# Screen.net
KiCad netlist of a schematic drawn in Altium Designer
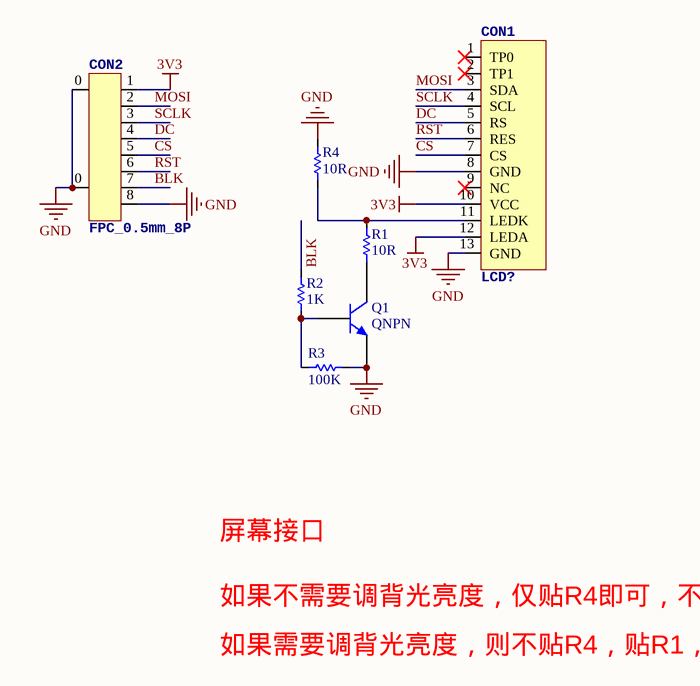
[diagram p0: Screen.SchDoc]

(export (version "E")
  (design (tool "Eeschema 10.0.6"))
  (components
    (comp (ref "CON1")
      (value "LCD?")
      (footprint "LCD_ST7735")
      (description "屏幕排线接口")
      (libsource (lib "Screen") (part "LCD_ST7735"))
    )
    (comp (ref "CON2")
      (value "FPC_0.5mm_8P")
      (footprint "FFC_0.5_8")
      (description "FPC连接器")
      (libsource (lib "Screen") (part "FPC_0.5mm_8P"))
    )
    (comp (ref "Q1")
      (value "QNPN")
      (footprint "SOT-23B_N")
      (description "NPN Bipolar Transistor")
      (fields (field (name "PUBLISHER") "Altium Limited"))
      (libsource (lib "Miscellaneous Devices") (part "QNPN"))
    )
    (comp (ref "R1")
      (value "10R")
      (footprint "RESC_0402")
      (description "贴片电阻")
      (libsource (lib "Screen") (part "电阻-0402"))
    )
    (comp (ref "R2")
      (value "1K")
      (footprint "RESC_0402")
      (description "贴片电阻")
      (libsource (lib "Screen") (part "电阻-0402"))
    )
    (comp (ref "R3")
      (value "100K")
      (footprint "RESC_0402")
      (description "贴片电阻")
      (libsource (lib "Screen") (part "电阻-0402"))
    )
    (comp (ref "R4")
      (value "10R")
      (footprint "RESC_0402")
      (description "贴片电阻")
      (libsource (lib "Screen") (part "电阻-0402"))
    )
  )
  (nets
    (net (code "1") (name "/BLK") (class "Default")
      (node (ref "CON2") (pin "7") (pinfunction "7_7") (pintype "passive"))
      (node (ref "R2") (pin "2") (pinfunction "2_2") (pintype "passive"))
    )
    (net (code "2") (name "/CS") (class "Default")
      (node (ref "CON1") (pin "7") (pinfunction "CS_7") (pintype "passive"))
      (node (ref "CON2") (pin "5") (pinfunction "5_5") (pintype "passive"))
    )
    (net (code "3") (name "/DC") (class "Default")
      (node (ref "CON1") (pin "5") (pinfunction "RS_5") (pintype "passive"))
      (node (ref "CON2") (pin "4") (pinfunction "4_4") (pintype "passive"))
    )
    (net (code "4") (name "/MOSI") (class "Default")
      (node (ref "CON1") (pin "3") (pinfunction "SDA_3") (pintype "passive"))
      (node (ref "CON2") (pin "2") (pinfunction "2_2") (pintype "passive"))
    )
    (net (code "5") (name "/RST") (class "Default")
      (node (ref "CON1") (pin "6") (pinfunction "RES_6") (pintype "passive"))
      (node (ref "CON2") (pin "6") (pinfunction "6_6") (pintype "passive"))
    )
    (net (code "6") (name "/SCLK") (class "Default")
      (node (ref "CON1") (pin "4") (pinfunction "SCL_4") (pintype "passive"))
      (node (ref "CON2") (pin "3") (pinfunction "3_3") (pintype "passive"))
    )
    (net (code "7") (name "3V3") (class "Default")
      (node (ref "CON1") (pin "10") (pinfunction "VCC_10") (pintype "passive"))
      (node (ref "CON1") (pin "12") (pinfunction "LEDA_12") (pintype "passive"))
      (node (ref "CON2") (pin "1") (pinfunction "1_1") (pintype "passive"))
    )
    (net (code "8") (name "GND") (class "Default")
      (node (ref "CON1") (pin "13") (pinfunction "GND_13") (pintype "passive"))
      (node (ref "CON1") (pin "8") (pinfunction "GND_8") (pintype "passive"))
      (node (ref "CON2") (pin "0") (pinfunction "0_0") (pintype "passive"))
      (node (ref "CON2") (pin "8") (pinfunction "8_8") (pintype "passive"))
      (node (ref "Q1") (pin "3") (pinfunction "E_3") (pintype "passive"))
      (node (ref "R3") (pin "2") (pinfunction "2_2") (pintype "passive"))
      (node (ref "R4") (pin "2") (pinfunction "2_2") (pintype "passive"))
    )
    (net (code "9") (name "Net-(CON1-LEDK)") (class "Default")
      (node (ref "CON1") (pin "11") (pinfunction "LEDK_11") (pintype "passive"))
      (node (ref "R1") (pin "2") (pinfunction "2_2") (pintype "passive"))
      (node (ref "R4") (pin "1") (pinfunction "1_1") (pintype "passive"))
    )
    (net (code "10") (name "Net-(Q1-B)") (class "Default")
      (node (ref "Q1") (pin "2") (pinfunction "B_2") (pintype "passive"))
      (node (ref "R2") (pin "1") (pinfunction "1_1") (pintype "passive"))
      (node (ref "R3") (pin "1") (pinfunction "1_1") (pintype "passive"))
    )
    (net (code "11") (name "Net-(Q1-C)") (class "Default")
      (node (ref "Q1") (pin "1") (pinfunction "C_1") (pintype "passive"))
      (node (ref "R1") (pin "1") (pinfunction "1_1") (pintype "passive"))
    )
    (net (code "12") (name "unconnected-(CON1-NC-Pad9)") (class "Default")
      (node (ref "CON1") (pin "9") (pinfunction "NC_9") (pintype "passive+no_connect"))
    )
    (net (code "13") (name "unconnected-(CON1-TP0-Pad1)") (class "Default")
      (node (ref "CON1") (pin "1") (pinfunction "TP0_1") (pintype "passive+no_connect"))
    )
    (net (code "14") (name "unconnected-(CON1-TP1-Pad2)") (class "Default")
      (node (ref "CON1") (pin "2") (pinfunction "TP1_2") (pintype "passive+no_connect"))
    )
  )
)
